# sch.net
KiCad netlist of a schematic drawn in EAGLE
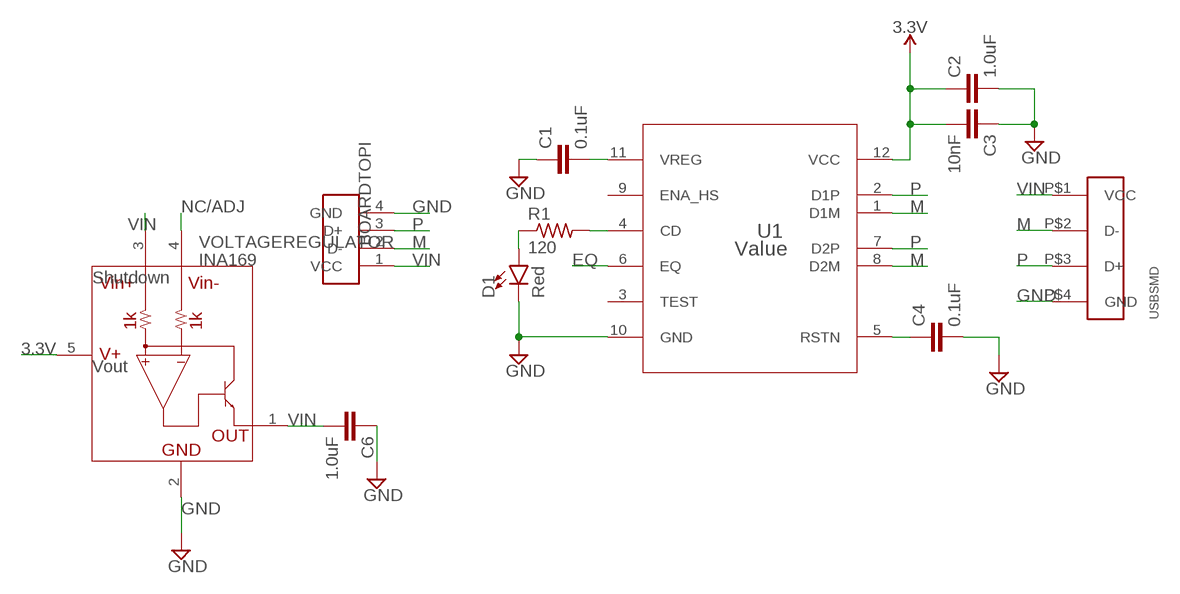
[diagram p0: schematic, sheet 1]

(export (version "E")
  (design (tool "Eeschema 10.0.6"))
  (components
    (comp (ref "BOARDTOPI")
      (value "USBPCB")
      (footprint "eagle-import:USBPCB")
      (libsource (lib "eagle-import") (part "USBPCB"))
    )
    (comp (ref "C1")
      (value "0.1uF")
      (footprint "eagle-import:0603")
      (libsource (lib "eagle-import") (part "0.1UF-0603-25V-(+80/-20%)"))
    )
    (comp (ref "C2")
      (value "1.0uF")
      (footprint "eagle-import:0603")
      (libsource (lib "eagle-import") (part "1.0UF-0603-16V-10%"))
    )
    (comp (ref "C3")
      (value "10nF")
      (footprint "eagle-import:0603")
      (libsource (lib "eagle-import") (part "10NF-0603-50V-10%"))
    )
    (comp (ref "C4")
      (value "0.1uF")
      (footprint "eagle-import:0603")
      (libsource (lib "eagle-import") (part "0.1UF-0603-25V-(+80/-20%)"))
    )
    (comp (ref "C6")
      (value "1.0uF")
      (footprint "eagle-import:0603")
      (libsource (lib "eagle-import") (part "1.0UF-0603-16V-10%"))
    )
    (comp (ref "D1")
      (value "Red")
      (footprint "eagle-import:LED-0603")
      (libsource (lib "eagle-import") (part "LED-RED0603-SMART"))
    )
    (comp (ref "R1")
      (value "120")
      (footprint "eagle-import:R0805")
      (libsource (lib "eagle-import") (part "R-US_R0805"))
    )
    (comp (ref "U1")
      (value "Value")
      (footprint "eagle-import:RWB0012A")
      (fields (field (name "MANUFACTURER") "Texas Instruments") (field (name "PARTNUMBER") "TUSB211QRWBR"))
      (libsource (lib "eagle-import") (part "TUSB211RWBR"))
    )
    (comp (ref "USBSMD")
      (value "USB")
      (footprint "eagle-import:USBSMD")
      (libsource (lib "eagle-import") (part "USB"))
    )
    (comp (ref "VOLTAGEREGULATOR")
      (value "INA169")
      (footprint "eagle-import:SOT23-5")
      (libsource (lib "eagle-import") (part "INA169"))
    )
  )
  (nets
    (net (code "1") (name "/EQ") (class "Default")
      (node (ref "U1") (pin "6") (pinfunction "EQ_6") (pintype "input"))
    )
    (net (code "2") (name "/M") (class "Default")
      (node (ref "BOARDTOPI") (pin "2") (pinfunction "D-_2") (pintype "bidirectional"))
      (node (ref "U1") (pin "1") (pinfunction "D1M_1") (pintype "bidirectional"))
      (node (ref "U1") (pin "8") (pinfunction "D2M_8") (pintype "bidirectional"))
      (node (ref "USBSMD") (pin "P$2") (pinfunction "D-_P$2") (pintype "bidirectional"))
    )
    (net (code "3") (name "/NC{slash}ADJ") (class "Default")
      (node (ref "VOLTAGEREGULATOR") (pin "4") (pinfunction "VIN-_4") (pintype "bidirectional"))
    )
    (net (code "4") (name "/P") (class "Default")
      (node (ref "BOARDTOPI") (pin "3") (pinfunction "D+_3") (pintype "bidirectional"))
      (node (ref "U1") (pin "2") (pinfunction "D1P_2") (pintype "bidirectional"))
      (node (ref "U1") (pin "7") (pinfunction "D2P_7") (pintype "bidirectional"))
      (node (ref "USBSMD") (pin "P$3") (pinfunction "D+_P$3") (pintype "bidirectional"))
    )
    (net (code "5") (name "/VIN") (class "Default")
      (node (ref "BOARDTOPI") (pin "1") (pinfunction "VCC_1") (pintype "bidirectional"))
      (node (ref "C6") (pin "2") (pinfunction "2_2") (pintype "passive"))
      (node (ref "USBSMD") (pin "P$1") (pinfunction "VCC_P$1") (pintype "bidirectional"))
      (node (ref "VOLTAGEREGULATOR") (pin "1") (pinfunction "OUT_1") (pintype "bidirectional"))
      (node (ref "VOLTAGEREGULATOR") (pin "3") (pinfunction "VIN+_3") (pintype "bidirectional"))
    )
    (net (code "6") (name "3.3V") (class "Default")
      (node (ref "C2") (pin "1") (pinfunction "1_1") (pintype "passive"))
      (node (ref "C3") (pin "2") (pinfunction "2_2") (pintype "passive"))
      (node (ref "U1") (pin "12") (pinfunction "VCC_12") (pintype "power_in"))
      (node (ref "VOLTAGEREGULATOR") (pin "5") (pinfunction "V+_5") (pintype "bidirectional"))
    )
    (net (code "7") (name "GND") (class "Default")
      (node (ref "BOARDTOPI") (pin "4") (pinfunction "GND_4") (pintype "bidirectional"))
      (node (ref "C1") (pin "1") (pinfunction "1_1") (pintype "passive"))
      (node (ref "C2") (pin "2") (pinfunction "2_2") (pintype "passive"))
      (node (ref "C3") (pin "1") (pinfunction "1_1") (pintype "passive"))
      (node (ref "C4") (pin "2") (pinfunction "2_2") (pintype "passive"))
      (node (ref "C6") (pin "1") (pinfunction "1_1") (pintype "passive"))
      (node (ref "D1") (pin "C") (pinfunction "C_C") (pintype "passive"))
      (node (ref "U1") (pin "10") (pinfunction "GND_10") (pintype "power_in"))
      (node (ref "USBSMD") (pin "P$4") (pinfunction "GND_P$4") (pintype "bidirectional"))
      (node (ref "VOLTAGEREGULATOR") (pin "2") (pinfunction "GND_2") (pintype "bidirectional"))
    )
    (net (code "8") (name "Net-(D1-PadA)") (class "Default")
      (node (ref "D1") (pin "A") (pinfunction "A_A") (pintype "passive"))
      (node (ref "R1") (pin "1") (pinfunction "1_1") (pintype "passive"))
    )
    (net (code "9") (name "Net-(U1-CD)") (class "Default")
      (node (ref "R1") (pin "2") (pinfunction "2_2") (pintype "passive"))
      (node (ref "U1") (pin "4") (pinfunction "CD_4") (pintype "output"))
    )
    (net (code "10") (name "Net-(U1-RSTN)") (class "Default")
      (node (ref "C4") (pin "1") (pinfunction "1_1") (pintype "passive"))
      (node (ref "U1") (pin "5") (pinfunction "RSTN_5") (pintype "input"))
    )
    (net (code "11") (name "Net-(U1-VREG)") (class "Default")
      (node (ref "C1") (pin "2") (pinfunction "2_2") (pintype "passive"))
      (node (ref "U1") (pin "11") (pinfunction "VREG_11") (pintype "power_in"))
    )
    (net (code "12") (name "unconnected-(U1-ENA_HS-Pad9)") (class "Default")
      (node (ref "U1") (pin "9") (pinfunction "ENA_HS_9") (pintype "output"))
    )
    (net (code "13") (name "unconnected-(U1-TEST-Pad3)") (class "Default")
      (node (ref "U1") (pin "3") (pinfunction "TEST_3") (pintype "passive"))
    )
  )
)
